# KMO_IO_MV2_2.net
KiCad netlist of a schematic drawn in EAGLE
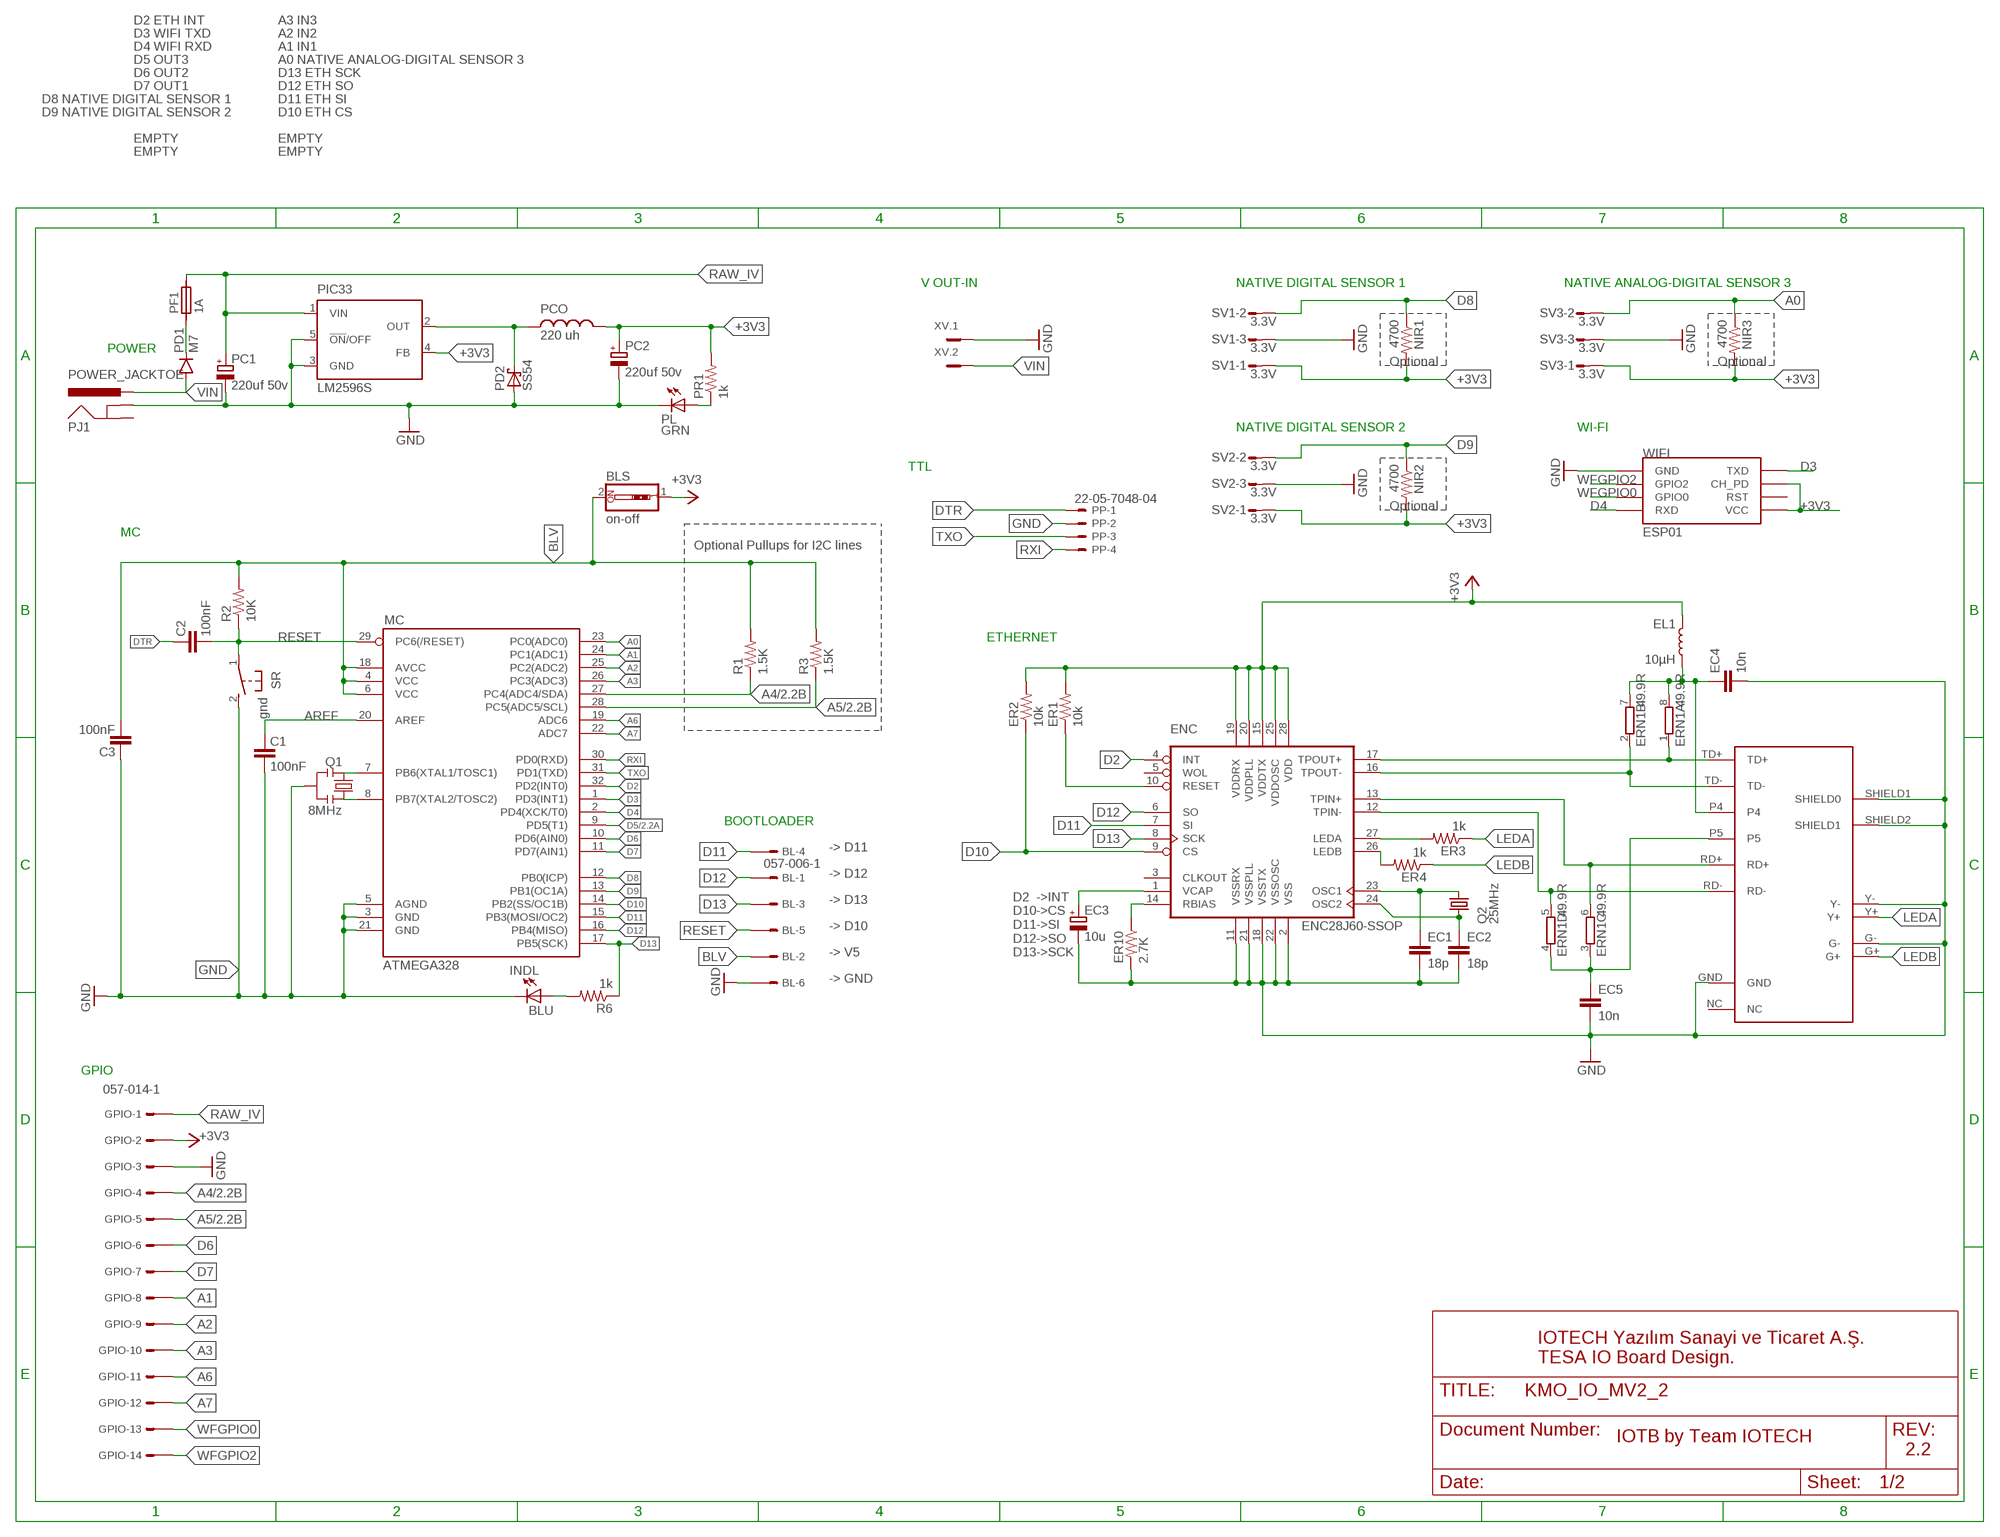
[diagram p0: schematic, sheet 1]
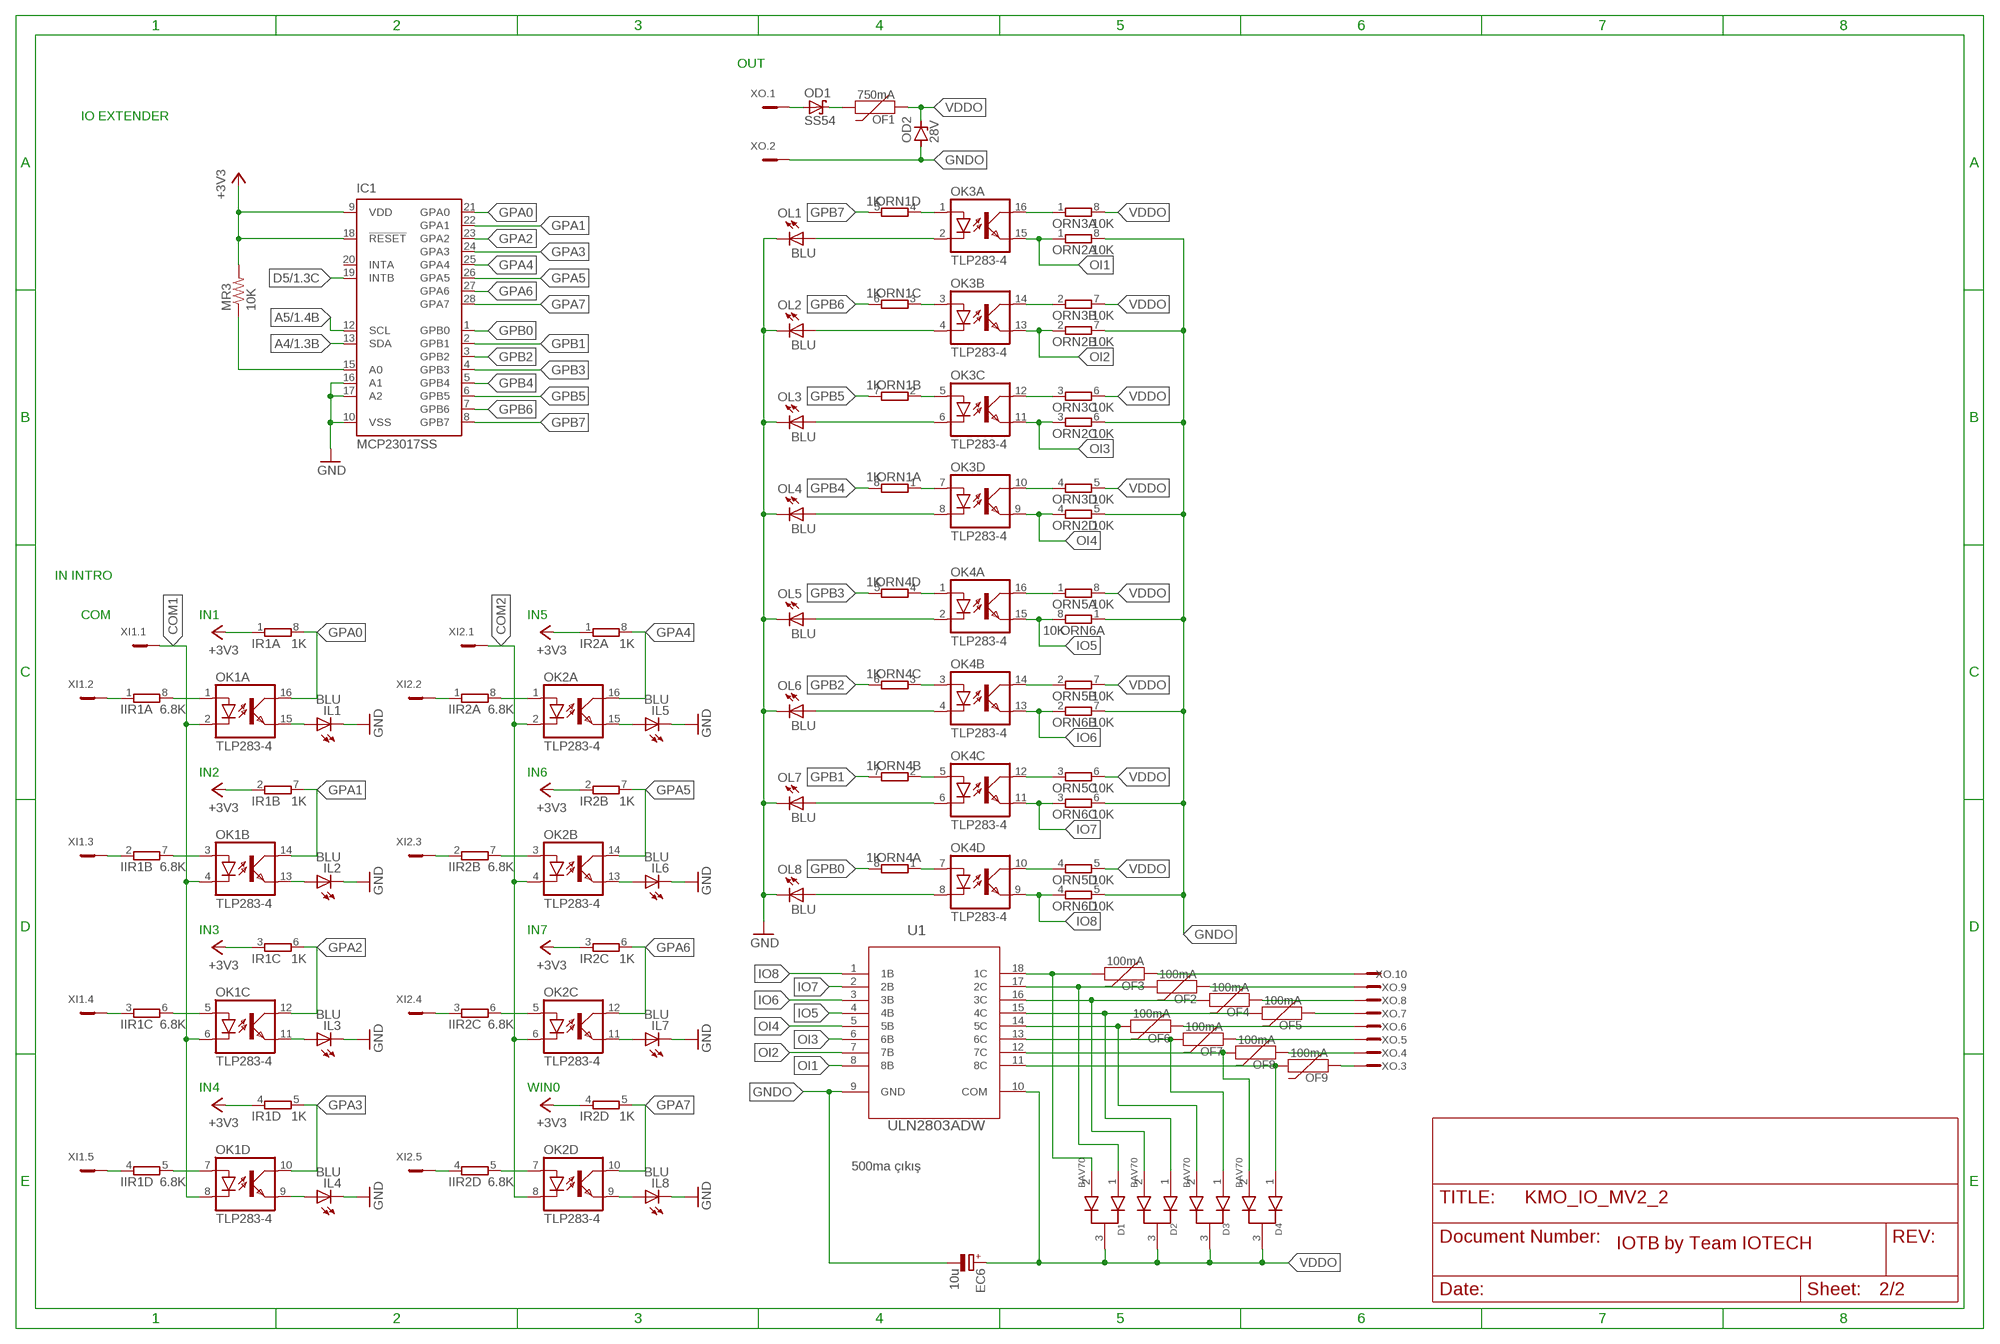
[diagram p1: schematic, sheet 2]

(export (version "E")
  (design (tool "Eeschema 10.0.6"))
  (components
    (comp (ref "BL")
      (value "057-006-1")
      (footprint "eagle-import:057-006-1")
      (libsource (lib "eagle-import") (part "057-006-1"))
    )
    (comp (ref "BLS")
      (value "on-off")
      (footprint "eagle-import:EDG-01")
      (libsource (lib "eagle-import") (part "SW_DIP-1"))
    )
    (comp (ref "C1")
      (value "100nF")
      (footprint "eagle-import:0805")
      (libsource (lib "eagle-import") (part "CAP0805"))
    )
    (comp (ref "C2")
      (value "100nF")
      (footprint "eagle-import:0805")
      (libsource (lib "eagle-import") (part "CAP0805"))
    )
    (comp (ref "C3")
      (value "100nF")
      (footprint "eagle-import:0805")
      (libsource (lib "eagle-import") (part "CAP0805"))
    )
    (comp (ref "EC1")
      (value "18p")
      (footprint "eagle-import:0805")
      (libsource (lib "eagle-import") (part "CAP0805"))
    )
    (comp (ref "EC2")
      (value "18p")
      (footprint "eagle-import:0805")
      (libsource (lib "eagle-import") (part "CAP0805"))
    )
    (comp (ref "EC3")
      (value "10u")
      (footprint "eagle-import:CT3216")
      (libsource (lib "eagle-import") (part "CPOL-EUCT3216"))
    )
    (comp (ref "EC4")
      (value "10n")
      (footprint "eagle-import:0805")
      (libsource (lib "eagle-import") (part "CAP0805"))
    )
    (comp (ref "EC5")
      (value "10n")
      (footprint "eagle-import:0805")
      (libsource (lib "eagle-import") (part "CAP0805"))
    )
    (comp (ref "EL1")
      (value "10µH")
      (footprint "eagle-import:0805")
      (libsource (lib "eagle-import") (part "INDUCTOR-0805-3.3UH"))
    )
    (comp (ref "ENC")
      (value "ENC28J60-SSOP")
      (footprint "eagle-import:SSOP28")
      (libsource (lib "eagle-import") (part "ENC28J60-SSOP"))
    )
    (comp (ref "ER1")
      (value "10k")
      (footprint "eagle-import:0805")
      (libsource (lib "eagle-import") (part "RESISTOR0805-RES"))
    )
    (comp (ref "ER2")
      (value "10k")
      (footprint "eagle-import:0805")
      (libsource (lib "eagle-import") (part "RESISTOR0805-RES"))
    )
    (comp (ref "ER3")
      (value "1k")
      (footprint "eagle-import:0805")
      (libsource (lib "eagle-import") (part "RESISTOR0805-RES"))
    )
    (comp (ref "ER4")
      (value "1k")
      (footprint "eagle-import:0805")
      (libsource (lib "eagle-import") (part "RESISTOR0805-RES"))
    )
    (comp (ref "ER10")
      (value "2.7K")
      (footprint "eagle-import:0805")
      (libsource (lib "eagle-import") (part "RESISTOR0805-RES"))
    )
    (comp (ref "ERN1")
      (value "49.9R")
      (footprint "eagle-import:0603-ARV")
      (libsource (lib "eagle-import") (part "4R-N0603-ARV"))
    )
    (comp (ref "GPIO")
      (value "057-014-1")
      (footprint "eagle-import:057-014-1")
      (libsource (lib "eagle-import") (part "057-014-1"))
    )
    (comp (ref "INDL")
      (value "BLU")
      (footprint "eagle-import:CHIP-LED0805")
      (libsource (lib "eagle-import") (part "LEDCHIP-LED0805"))
    )
    (comp (ref "MC")
      (value "ATMEGA328")
      (footprint "eagle-import:TQFP32-08")
      (libsource (lib "eagle-import") (part "ATMEGA168"))
    )
    (comp (ref "NIR1")
      (value "4700")
      (footprint "eagle-import:0805")
      (libsource (lib "eagle-import") (part "RESISTOR0805-RES"))
    )
    (comp (ref "NIR2")
      (value "4700")
      (footprint "eagle-import:0805")
      (libsource (lib "eagle-import") (part "RESISTOR0805-RES"))
    )
    (comp (ref "NIR3")
      (value "4700")
      (footprint "eagle-import:0805")
      (libsource (lib "eagle-import") (part "RESISTOR0805-RES"))
    )
    (comp (ref "PC1")
      (value "220uf 50v")
      (footprint "eagle-import:140CLH-1010")
      (libsource (lib "eagle-import") (part "CPOL-EU140CLH-1010"))
    )
    (comp (ref "PC2")
      (value "220uf 50v")
      (footprint "eagle-import:140CLH-1010")
      (libsource (lib "eagle-import") (part "CPOL-EU140CLH-1010"))
    )
    (comp (ref "PCO")
      (value "220 uh")
      (footprint "eagle-import:MSS1260")
      (libsource (lib "eagle-import") (part "MSS1260"))
    )
    (comp (ref "PD1")
      (value "M7")
      (footprint "eagle-import:SMA-DIODE")
      (libsource (lib "eagle-import") (part "DIODESMA"))
    )
    (comp (ref "PD2")
      (value "SS54")
      (footprint "eagle-import:SMB")
      (libsource (lib "eagle-import") (part "SCHOTTKY-DIODESMD"))
    )
    (comp (ref "PF1")
      (value "1A")
      (footprint "eagle-import:1820")
      (libsource (lib "eagle-import") (part "SIBA194600"))
    )
    (comp (ref "PIC33")
      (value "LM2596S")
      (footprint "eagle-import:TO263-5")
      (fields (field (name "MF") "NATIONAL SEMICONDUCTOR") (field (name "MPN") "LM2596S-ADJ/NOPB"))
      (libsource (lib "eagle-import") (part "LM2596S"))
    )
    (comp (ref "PJ1")
      (value "POWER_JACKTOE")
      (footprint "eagle-import:POWER_JACK_SMD_OVERPASTE_TOE")
      (libsource (lib "eagle-import") (part "POWER_JACKTOE"))
    )
    (comp (ref "PL")
      (value "GRN")
      (footprint "eagle-import:CHIP-LED0805")
      (libsource (lib "eagle-import") (part "LEDCHIP-LED0805"))
    )
    (comp (ref "PP")
      (value "22-05-7048-04")
      (footprint "eagle-import:7395-04")
      (fields (field (name "MF") "MOLEX"))
      (libsource (lib "eagle-import") (part "22-?-0405-7048"))
    )
    (comp (ref "PR1")
      (value "1k")
      (footprint "eagle-import:0805")
      (libsource (lib "eagle-import") (part "RESISTOR0805-RES"))
    )
    (comp (ref "Q1")
      (value "8MHz")
      (footprint "eagle-import:RESONATOR-SMD-1_1")
      (libsource (lib "eagle-import") (part "RESONATOR1{colon}1"))
    )
    (comp (ref "Q2")
      (value "25MHz")
      (footprint "eagle-import:5.0X3.2_2")
      (libsource (lib "eagle-import") (part "KX-9B"))
    )
    (comp (ref "R1")
      (value "1.5K")
      (footprint "eagle-import:0805")
      (libsource (lib "eagle-import") (part "RESISTOR0805-RES"))
    )
    (comp (ref "R2")
      (value "10K")
      (footprint "eagle-import:0805")
      (libsource (lib "eagle-import") (part "RESISTOR0805-RES"))
    )
    (comp (ref "R3")
      (value "1.5K")
      (footprint "eagle-import:0805")
      (libsource (lib "eagle-import") (part "RESISTOR0805-RES"))
    )
    (comp (ref "R6")
      (value "1k")
      (footprint "eagle-import:0805")
      (libsource (lib "eagle-import") (part "RESISTOR0805-RES"))
    )
    (comp (ref "SR")
      (value "gnd")
      (footprint "eagle-import:B3F-31XX")
      (fields (field (name "MPN") "B3F-3100"))
      (libsource (lib "eagle-import") (part "31-XX"))
    )
    (comp (ref "SV1")
      (value "3.3V")
      (footprint "eagle-import:S03P")
      (libsource (lib "eagle-import") (part "S03P"))
    )
    (comp (ref "SV2")
      (value "3.3V")
      (footprint "eagle-import:S03P")
      (libsource (lib "eagle-import") (part "S03P"))
    )
    (comp (ref "SV3")
      (value "3.3V")
      (footprint "eagle-import:S03P")
      (libsource (lib "eagle-import") (part "S03P"))
    )
    (comp (ref "U$2")
      (value "HR911105A")
      (footprint "eagle-import:RJ45")
      (libsource (lib "eagle-import") (part "HR911105A"))
    )
    (comp (ref "WIFI")
      (value "ESP01")
      (footprint "eagle-import:ESP01")
      (libsource (lib "eagle-import") (part "ESP01"))
    )
    (comp (ref "XV")
      (value "MC2")
      (footprint "eagle-import:MC2")
      (libsource (lib "eagle-import") (part "MC2"))
    )
    (comp (ref "D1")
      (value "BAV70")
      (footprint "eagle-import:SOT-23-3")
      (fields (field (name "MF") "Multicomp") (field (name "MP") "BAV70+"))
      (libsource (lib "eagle-import") (part "BAV70"))
    )
    (comp (ref "D2")
      (value "BAV70")
      (footprint "eagle-import:SOT-23-3")
      (fields (field (name "MF") "Multicomp") (field (name "MP") "BAV70+"))
      (libsource (lib "eagle-import") (part "BAV70"))
    )
    (comp (ref "D3")
      (value "BAV70")
      (footprint "eagle-import:SOT-23-3")
      (fields (field (name "MF") "Multicomp") (field (name "MP") "BAV70+"))
      (libsource (lib "eagle-import") (part "BAV70"))
    )
    (comp (ref "D4")
      (value "BAV70")
      (footprint "eagle-import:SOT-23-3")
      (fields (field (name "MF") "Multicomp") (field (name "MP") "BAV70+"))
      (libsource (lib "eagle-import") (part "BAV70"))
    )
    (comp (ref "EC6")
      (value "10u")
      (footprint "eagle-import:CT3216")
      (libsource (lib "eagle-import") (part "CPOL-EUCT3216"))
    )
    (comp (ref "IC1")
      (value "MCP23017SS")
      (footprint "eagle-import:SSOP28")
      (fields (field (name "MF") "MICROCHIP") (field (name "MPN") "MCP23017-E/SS"))
      (libsource (lib "eagle-import") (part "MCP23017SS"))
    )
    (comp (ref "IIR1")
      (value "6.8K")
      (footprint "eagle-import:0603-ARV")
      (libsource (lib "eagle-import") (part "4R-N0603-ARV"))
    )
    (comp (ref "IIR2")
      (value "6.8K")
      (footprint "eagle-import:0603-ARV")
      (libsource (lib "eagle-import") (part "4R-N0603-ARV"))
    )
    (comp (ref "IL1")
      (value "BLU")
      (footprint "eagle-import:CHIP-LED0805")
      (libsource (lib "eagle-import") (part "LEDCHIP-LED0805"))
    )
    (comp (ref "IL2")
      (value "BLU")
      (footprint "eagle-import:CHIP-LED0805")
      (libsource (lib "eagle-import") (part "LEDCHIP-LED0805"))
    )
    (comp (ref "IL3")
      (value "BLU")
      (footprint "eagle-import:CHIP-LED0805")
      (libsource (lib "eagle-import") (part "LEDCHIP-LED0805"))
    )
    (comp (ref "IL4")
      (value "BLU")
      (footprint "eagle-import:CHIP-LED0805")
      (libsource (lib "eagle-import") (part "LEDCHIP-LED0805"))
    )
    (comp (ref "IL5")
      (value "BLU")
      (footprint "eagle-import:CHIP-LED0805")
      (libsource (lib "eagle-import") (part "LEDCHIP-LED0805"))
    )
    (comp (ref "IL6")
      (value "BLU")
      (footprint "eagle-import:CHIP-LED0805")
      (libsource (lib "eagle-import") (part "LEDCHIP-LED0805"))
    )
    (comp (ref "IL7")
      (value "BLU")
      (footprint "eagle-import:CHIP-LED0805")
      (libsource (lib "eagle-import") (part "LEDCHIP-LED0805"))
    )
    (comp (ref "IL8")
      (value "BLU")
      (footprint "eagle-import:CHIP-LED0805")
      (libsource (lib "eagle-import") (part "LEDCHIP-LED0805"))
    )
    (comp (ref "IR1")
      (value "1K")
      (footprint "eagle-import:0603-ARV")
      (libsource (lib "eagle-import") (part "4R-N0603-ARV"))
    )
    (comp (ref "IR2")
      (value "1K")
      (footprint "eagle-import:0603-ARV")
      (libsource (lib "eagle-import") (part "4R-N0603-ARV"))
    )
    (comp (ref "MR3")
      (value "10K")
      (footprint "eagle-import:0805")
      (libsource (lib "eagle-import") (part "RESISTOR0805-RES"))
    )
    (comp (ref "OD1")
      (value "SS54")
      (footprint "eagle-import:SMB")
      (libsource (lib "eagle-import") (part "SCHOTTKY-DIODESMD"))
    )
    (comp (ref "OD2")
      (value "28V")
      (footprint "eagle-import:SMB")
      (libsource (lib "eagle-import") (part "ZENER-DIODESMB"))
    )
    (comp (ref "OF1")
      (value "750mA")
      (footprint "eagle-import:1206")
      (libsource (lib "eagle-import") (part "PPTC_0.75A"))
    )
    (comp (ref "OF2")
      (value "100mA")
      (footprint "eagle-import:1206")
      (libsource (lib "eagle-import") (part "PPTC_0.75A"))
    )
    (comp (ref "OF3")
      (value "100mA")
      (footprint "eagle-import:1206")
      (libsource (lib "eagle-import") (part "PPTC_0.75A"))
    )
    (comp (ref "OF4")
      (value "100mA")
      (footprint "eagle-import:1206")
      (libsource (lib "eagle-import") (part "PPTC_0.75A"))
    )
    (comp (ref "OF5")
      (value "100mA")
      (footprint "eagle-import:1206")
      (libsource (lib "eagle-import") (part "PPTC_0.75A"))
    )
    (comp (ref "OF6")
      (value "100mA")
      (footprint "eagle-import:1206")
      (libsource (lib "eagle-import") (part "PPTC_0.75A"))
    )
    (comp (ref "OF7")
      (value "100mA")
      (footprint "eagle-import:1206")
      (libsource (lib "eagle-import") (part "PPTC_0.75A"))
    )
    (comp (ref "OF8")
      (value "100mA")
      (footprint "eagle-import:1206")
      (libsource (lib "eagle-import") (part "PPTC_0.75A"))
    )
    (comp (ref "OF9")
      (value "100mA")
      (footprint "eagle-import:1206")
      (libsource (lib "eagle-import") (part "PPTC_0.75A"))
    )
    (comp (ref "OK1")
      (value "TLP283-4")
      (footprint "eagle-import:MINI-FLAT-16")
      (fields (field (name "SPICEPREFIX") "O"))
      (libsource (lib "eagle-import") (part "TLP283-4"))
    )
    (comp (ref "OK2")
      (value "TLP283-4")
      (footprint "eagle-import:MINI-FLAT-16")
      (fields (field (name "SPICEPREFIX") "O"))
      (libsource (lib "eagle-import") (part "TLP283-4"))
    )
    (comp (ref "OK3")
      (value "TLP283-4")
      (footprint "eagle-import:MINI-FLAT-16")
      (libsource (lib "eagle-import") (part "TLP283-4"))
    )
    (comp (ref "OK4")
      (value "TLP283-4")
      (footprint "eagle-import:MINI-FLAT-16")
      (libsource (lib "eagle-import") (part "TLP283-4"))
    )
    (comp (ref "OL1")
      (value "BLU")
      (footprint "eagle-import:CHIP-LED0805")
      (libsource (lib "eagle-import") (part "LEDCHIP-LED0805"))
    )
    (comp (ref "OL2")
      (value "BLU")
      (footprint "eagle-import:CHIP-LED0805")
      (libsource (lib "eagle-import") (part "LEDCHIP-LED0805"))
    )
    (comp (ref "OL3")
      (value "BLU")
      (footprint "eagle-import:CHIP-LED0805")
      (libsource (lib "eagle-import") (part "LEDCHIP-LED0805"))
    )
    (comp (ref "OL4")
      (value "BLU")
      (footprint "eagle-import:CHIP-LED0805")
      (libsource (lib "eagle-import") (part "LEDCHIP-LED0805"))
    )
    (comp (ref "OL5")
      (value "BLU")
      (footprint "eagle-import:CHIP-LED0805")
      (libsource (lib "eagle-import") (part "LEDCHIP-LED0805"))
    )
    (comp (ref "OL6")
      (value "BLU")
      (footprint "eagle-import:CHIP-LED0805")
      (libsource (lib "eagle-import") (part "LEDCHIP-LED0805"))
    )
    (comp (ref "OL7")
      (value "BLU")
      (footprint "eagle-import:CHIP-LED0805")
      (libsource (lib "eagle-import") (part "LEDCHIP-LED0805"))
    )
    (comp (ref "OL8")
      (value "BLU")
      (footprint "eagle-import:CHIP-LED0805")
      (libsource (lib "eagle-import") (part "LEDCHIP-LED0805"))
    )
    (comp (ref "ORN1")
      (value "1K")
      (footprint "eagle-import:0603-ARV")
      (libsource (lib "eagle-import") (part "4R-N0603-ARV"))
    )
    (comp (ref "ORN2")
      (value "10K")
      (footprint "eagle-import:0603-ARV")
      (libsource (lib "eagle-import") (part "4R-N0603-ARV"))
    )
    (comp (ref "ORN3")
      (value "10K")
      (footprint "eagle-import:0603-ARV")
      (libsource (lib "eagle-import") (part "4R-N0603-ARV"))
    )
    (comp (ref "ORN4")
      (value "1K")
      (footprint "eagle-import:0603-ARV")
      (libsource (lib "eagle-import") (part "4R-N0603-ARV"))
    )
    (comp (ref "ORN5")
      (value "10K")
      (footprint "eagle-import:0603-ARV")
      (libsource (lib "eagle-import") (part "4R-N0603-ARV"))
    )
    (comp (ref "ORN6")
      (value "10K")
      (footprint "eagle-import:0603-ARV")
      (libsource (lib "eagle-import") (part "4R-N0603-ARV"))
    )
    (comp (ref "U1")
      (value "ULN2803ADW")
      (footprint "eagle-import:SOIC127P1030X265-18N")
      (libsource (lib "eagle-import") (part "ULN2803ADW"))
    )
    (comp (ref "XI1")
      (value "MC5")
      (footprint "eagle-import:MC5")
      (libsource (lib "eagle-import") (part "MC5"))
    )
    (comp (ref "XI2")
      (value "MC5")
      (footprint "eagle-import:MC5")
      (libsource (lib "eagle-import") (part "MC5"))
    )
    (comp (ref "XO")
      (value "MC10")
      (footprint "eagle-import:MC10")
      (libsource (lib "eagle-import") (part "MC10"))
    )
  )
  (nets
    (net (code "1") (name "+3V3") (class "Default")
      (node (ref "BLS") (pin "1") (pinfunction "1_1") (pintype "passive"))
      (node (ref "EL1") (pin "1") (pinfunction "1_1") (pintype "passive"))
      (node (ref "ENC") (pin "15") (pinfunction "VDDTX_15") (pintype "power_in"))
      (node (ref "ENC") (pin "19") (pinfunction "VDDRX_19") (pintype "power_in"))
      (node (ref "ENC") (pin "20") (pinfunction "VDDPLL_20") (pintype "power_in"))
      (node (ref "ENC") (pin "25") (pinfunction "VDDOSC_25") (pintype "power_in"))
      (node (ref "ENC") (pin "28") (pinfunction "VDD_28") (pintype "power_in"))
      (node (ref "ER1") (pin "2") (pinfunction "2_2") (pintype "passive"))
      (node (ref "ER2") (pin "2") (pinfunction "2_2") (pintype "passive"))
      (node (ref "GPIO") (pin "2") (pinfunction "S_2") (pintype "passive"))
      (node (ref "IC1") (pin "18") (pinfunction "~{RESET}_18") (pintype "input"))
      (node (ref "IC1") (pin "9") (pinfunction "VDD_9") (pintype "power_in"))
      (node (ref "IR1") (pin "1") (pinfunction "1_1") (pintype "passive"))
      (node (ref "IR1") (pin "2") (pinfunction "1_2") (pintype "passive"))
      (node (ref "IR1") (pin "3") (pinfunction "1_3") (pintype "passive"))
      (node (ref "IR1") (pin "4") (pinfunction "1_4") (pintype "passive"))
      (node (ref "IR2") (pin "1") (pinfunction "1_1") (pintype "passive"))
      (node (ref "IR2") (pin "2") (pinfunction "1_2") (pintype "passive"))
      (node (ref "IR2") (pin "3") (pinfunction "1_3") (pintype "passive"))
      (node (ref "IR2") (pin "4") (pinfunction "1_4") (pintype "passive"))
      (node (ref "MR3") (pin "2") (pinfunction "2_2") (pintype "passive"))
      (node (ref "NIR1") (pin "2") (pinfunction "2_2") (pintype "passive"))
      (node (ref "NIR2") (pin "2") (pinfunction "2_2") (pintype "passive"))
      (node (ref "NIR3") (pin "2") (pinfunction "2_2") (pintype "passive"))
      (node (ref "PC2") (pin "+") (pinfunction "+_+") (pintype "passive"))
      (node (ref "PCO") (pin "P$1") (pinfunction "P$1_P$1") (pintype "passive"))
      (node (ref "PIC33") (pin "4") (pinfunction "FB_4") (pintype "input"))
      (node (ref "PR1") (pin "2") (pinfunction "2_2") (pintype "passive"))
      (node (ref "SV1") (pin "1") (pinfunction "S_1") (pintype "passive"))
      (node (ref "SV2") (pin "1") (pinfunction "S_1") (pintype "passive"))
      (node (ref "SV3") (pin "1") (pinfunction "S_1") (pintype "passive"))
      (node (ref "WIFI") (pin "CH_PD") (pinfunction "CH_PD_CH_PD") (pintype "bidirectional"))
      (node (ref "WIFI") (pin "VCC") (pinfunction "VCC_VCC") (pintype "bidirectional"))
    )
    (net (code "2") (name "A0") (class "Default")
      (node (ref "MC") (pin "23") (pinfunction "PC0(ADC0)_23") (pintype "bidirectional"))
      (node (ref "NIR3") (pin "1") (pinfunction "1_1") (pintype "passive"))
      (node (ref "SV3") (pin "2") (pinfunction "S_2") (pintype "passive"))
    )
    (net (code "3") (name "A1") (class "Default")
      (node (ref "GPIO") (pin "8") (pinfunction "S_8") (pintype "passive"))
      (node (ref "MC") (pin "24") (pinfunction "PC1(ADC1)_24") (pintype "bidirectional"))
    )
    (net (code "4") (name "A2") (class "Default")
      (node (ref "GPIO") (pin "9") (pinfunction "S_9") (pintype "passive"))
      (node (ref "MC") (pin "25") (pinfunction "PC2(ADC2)_25") (pintype "bidirectional"))
    )
    (net (code "5") (name "A3") (class "Default")
      (node (ref "GPIO") (pin "10") (pinfunction "S_10") (pintype "passive"))
      (node (ref "MC") (pin "26") (pinfunction "PC3(ADC3)_26") (pintype "bidirectional"))
    )
    (net (code "6") (name "A4") (class "Default")
      (node (ref "GPIO") (pin "4") (pinfunction "S_4") (pintype "passive"))
      (node (ref "IC1") (pin "13") (pinfunction "SDA_13") (pintype "bidirectional"))
      (node (ref "MC") (pin "27") (pinfunction "PC4(ADC4/SDA)_27") (pintype "bidirectional"))
      (node (ref "R1") (pin "1") (pinfunction "1_1") (pintype "passive"))
    )
    (net (code "7") (name "A5") (class "Default")
      (node (ref "GPIO") (pin "5") (pinfunction "S_5") (pintype "passive"))
      (node (ref "IC1") (pin "12") (pinfunction "SCL_12") (pintype "input"))
      (node (ref "MC") (pin "28") (pinfunction "PC5(ADC5/SCL)_28") (pintype "bidirectional"))
      (node (ref "R3") (pin "1") (pinfunction "1_1") (pintype "passive"))
    )
    (net (code "8") (name "A6") (class "Default")
      (node (ref "GPIO") (pin "11") (pinfunction "S_11") (pintype "passive"))
      (node (ref "MC") (pin "19") (pinfunction "ADC6_19") (pintype "bidirectional"))
    )
    (net (code "9") (name "A7") (class "Default")
      (node (ref "GPIO") (pin "12") (pinfunction "S_12") (pintype "passive"))
      (node (ref "MC") (pin "22") (pinfunction "ADC7_22") (pintype "bidirectional"))
    )
    (net (code "10") (name "AREF") (class "Default")
      (node (ref "C1") (pin "2") (pinfunction "2_2") (pintype "passive"))
      (node (ref "MC") (pin "20") (pinfunction "AREF_20") (pintype "bidirectional"))
    )
    (net (code "11") (name "BLV") (class "Default")
      (node (ref "BL") (pin "2") (pinfunction "S_2") (pintype "passive"))
      (node (ref "BLS") (pin "2") (pinfunction "2_2") (pintype "passive"))
      (node (ref "C3") (pin "1") (pinfunction "1_1") (pintype "passive"))
      (node (ref "MC") (pin "18") (pinfunction "AVCC_18") (pintype "bidirectional"))
      (node (ref "MC") (pin "4") (pinfunction "VCC_4") (pintype "bidirectional"))
      (node (ref "MC") (pin "6") (pinfunction "VCC_6") (pintype "bidirectional"))
      (node (ref "R1") (pin "2") (pinfunction "2_2") (pintype "passive"))
      (node (ref "R2") (pin "2") (pinfunction "2_2") (pintype "passive"))
      (node (ref "R3") (pin "2") (pinfunction "2_2") (pintype "passive"))
    )
    (net (code "12") (name "COM1") (class "Default")
      (node (ref "OK1") (pin "2") (pinfunction "C_2") (pintype "passive"))
      (node (ref "OK1") (pin "4") (pinfunction "C_4") (pintype "passive"))
      (node (ref "OK1") (pin "6") (pinfunction "C_6") (pintype "passive"))
      (node (ref "OK1") (pin "8") (pinfunction "C_8") (pintype "passive"))
      (node (ref "XI1") (pin "1") (pinfunction "SK_1") (pintype "passive"))
    )
    (net (code "13") (name "COM2") (class "Default")
      (node (ref "OK2") (pin "2") (pinfunction "C_2") (pintype "passive"))
      (node (ref "OK2") (pin "4") (pinfunction "C_4") (pintype "passive"))
      (node (ref "OK2") (pin "6") (pinfunction "C_6") (pintype "passive"))
      (node (ref "OK2") (pin "8") (pinfunction "C_8") (pintype "passive"))
      (node (ref "XI2") (pin "1") (pinfunction "SK_1") (pintype "passive"))
    )
    (net (code "14") (name "D2") (class "Default")
      (node (ref "ENC") (pin "4") (pinfunction "INT_4") (pintype "output"))
      (node (ref "MC") (pin "32") (pinfunction "PD2(INT0)_32") (pintype "bidirectional"))
    )
    (net (code "15") (name "D3") (class "Default")
      (node (ref "MC") (pin "1") (pinfunction "PD3(INT1)_1") (pintype "bidirectional"))
      (node (ref "WIFI") (pin "TX") (pinfunction "TXD_TX") (pintype "bidirectional"))
    )
    (net (code "16") (name "D4") (class "Default")
      (node (ref "MC") (pin "2") (pinfunction "PD4(XCK/T0)_2") (pintype "bidirectional"))
      (node (ref "WIFI") (pin "RX") (pinfunction "RXD_RX") (pintype "bidirectional"))
    )
    (net (code "17") (name "D5") (class "Default")
      (node (ref "IC1") (pin "19") (pinfunction "INTB_19") (pintype "output"))
      (node (ref "MC") (pin "9") (pinfunction "PD5(T1)_9") (pintype "bidirectional"))
    )
    (net (code "18") (name "D6") (class "Default")
      (node (ref "GPIO") (pin "6") (pinfunction "S_6") (pintype "passive"))
      (node (ref "MC") (pin "10") (pinfunction "PD6(AIN0)_10") (pintype "bidirectional"))
    )
    (net (code "19") (name "D7") (class "Default")
      (node (ref "GPIO") (pin "7") (pinfunction "S_7") (pintype "passive"))
      (node (ref "MC") (pin "11") (pinfunction "PD7(AIN1)_11") (pintype "bidirectional"))
    )
    (net (code "20") (name "D8") (class "Default")
      (node (ref "MC") (pin "12") (pinfunction "PB0(ICP)_12") (pintype "bidirectional"))
      (node (ref "NIR1") (pin "1") (pinfunction "1_1") (pintype "passive"))
      (node (ref "SV1") (pin "2") (pinfunction "S_2") (pintype "passive"))
    )
    (net (code "21") (name "D9") (class "Default")
      (node (ref "MC") (pin "13") (pinfunction "PB1(OC1A)_13") (pintype "bidirectional"))
      (node (ref "NIR2") (pin "1") (pinfunction "1_1") (pintype "passive"))
      (node (ref "SV2") (pin "2") (pinfunction "S_2") (pintype "passive"))
    )
    (net (code "22") (name "D10") (class "Default")
      (node (ref "ENC") (pin "9") (pinfunction "CS_9") (pintype "input"))
      (node (ref "ER2") (pin "1") (pinfunction "1_1") (pintype "passive"))
      (node (ref "MC") (pin "14") (pinfunction "PB2(SS/OC1B)_14") (pintype "bidirectional"))
    )
    (net (code "23") (name "D11") (class "Default")
      (node (ref "BL") (pin "4") (pinfunction "S_4") (pintype "passive"))
      (node (ref "ENC") (pin "7") (pinfunction "SI_7") (pintype "input"))
      (node (ref "MC") (pin "15") (pinfunction "PB3(MOSI/OC2)_15") (pintype "bidirectional"))
    )
    (net (code "24") (name "D12") (class "Default")
      (node (ref "BL") (pin "1") (pinfunction "S_1") (pintype "passive"))
      (node (ref "ENC") (pin "6") (pinfunction "SO_6") (pintype "output"))
      (node (ref "MC") (pin "16") (pinfunction "PB4(MISO)_16") (pintype "bidirectional"))
    )
    (net (code "25") (name "D13") (class "Default")
      (node (ref "BL") (pin "3") (pinfunction "S_3") (pintype "passive"))
      (node (ref "ENC") (pin "8") (pinfunction "SCK_8") (pintype "input"))
      (node (ref "MC") (pin "17") (pinfunction "PB5(SCK)_17") (pintype "bidirectional"))
      (node (ref "R6") (pin "1") (pinfunction "1_1") (pintype "passive"))
    )
    (net (code "26") (name "DTR") (class "Default")
      (node (ref "C2") (pin "2") (pinfunction "2_2") (pintype "passive"))
      (node (ref "PP") (pin "1") (pinfunction "S_1") (pintype "passive"))
    )
    (net (code "27") (name "GND") (class "Default")
      (node (ref "BL") (pin "6") (pinfunction "S_6") (pintype "passive"))
      (node (ref "C1") (pin "1") (pinfunction "1_1") (pintype "passive"))
      (node (ref "C3") (pin "2") (pinfunction "2_2") (pintype "passive"))
      (node (ref "EC1") (pin "2") (pinfunction "2_2") (pintype "passive"))
      (node (ref "EC2") (pin "2") (pinfunction "2_2") (pintype "passive"))
      (node (ref "EC3") (pin "-") (pinfunction "-_-") (pintype "passive"))
      (node (ref "EC4") (pin "2") (pinfunction "2_2") (pintype "passive"))
      (node (ref "EC5") (pin "2") (pinfunction "2_2") (pintype "passive"))
      (node (ref "ENC") (pin "11") (pinfunction "VSSRX_11") (pintype "power_in"))
      (node (ref "ENC") (pin "18") (pinfunction "VSSTX_18") (pintype "power_in"))
      (node (ref "ENC") (pin "2") (pinfunction "VSS_2") (pintype "power_in"))
      (node (ref "ENC") (pin "21") (pinfunction "VSSPLL_21") (pintype "power_in"))
      (node (ref "ENC") (pin "22") (pinfunction "VSSOSC_22") (pintype "power_in"))
      (node (ref "ER10") (pin "2") (pinfunction "2_2") (pintype "passive"))
      (node (ref "GPIO") (pin "3") (pinfunction "S_3") (pintype "passive"))
      (node (ref "IC1") (pin "10") (pinfunction "VSS_10") (pintype "power_in"))
      (node (ref "IC1") (pin "16") (pinfunction "A1_16") (pintype "input"))
      (node (ref "IC1") (pin "17") (pinfunction "A2_17") (pintype "input"))
      (node (ref "IL1") (pin "C") (pinfunction "C_C") (pintype "passive"))
      (node (ref "IL2") (pin "C") (pinfunction "C_C") (pintype "passive"))
      (node (ref "IL3") (pin "C") (pinfunction "C_C") (pintype "passive"))
      (node (ref "IL4") (pin "C") (pinfunction "C_C") (pintype "passive"))
      (node (ref "IL5") (pin "C") (pinfunction "C_C") (pintype "passive"))
      (node (ref "IL6") (pin "C") (pinfunction "C_C") (pintype "passive"))
      (node (ref "IL7") (pin "C") (pinfunction "C_C") (pintype "passive"))
      (node (ref "IL8") (pin "C") (pinfunction "C_C") (pintype "passive"))
      (node (ref "INDL") (pin "C") (pinfunction "C_C") (pintype "passive"))
      (node (ref "MC") (pin "21") (pinfunction "GND_21") (pintype "bidirectional"))
      (node (ref "MC") (pin "3") (pinfunction "GND_3") (pintype "bidirectional"))
      (node (ref "MC") (pin "5") (pinfunction "AGND_5") (pintype "bidirectional"))
      (node (ref "OL1") (pin "C") (pinfunction "C_C") (pintype "passive"))
      (node (ref "OL2") (pin "C") (pinfunction "C_C") (pintype "passive"))
      (node (ref "OL3") (pin "C") (pinfunction "C_C") (pintype "passive"))
      (node (ref "OL4") (pin "C") (pinfunction "C_C") (pintype "passive"))
      (node (ref "OL5") (pin "C") (pinfunction "C_C") (pintype "passive"))
      (node (ref "OL6") (pin "C") (pinfunction "C_C") (pintype "passive"))
      (node (ref "OL7") (pin "C") (pinfunction "C_C") (pintype "passive"))
      (node (ref "OL8") (pin "C") (pinfunction "C_C") (pintype "passive"))
      (node (ref "PC1") (pin "-") (pinfunction "-_-") (pintype "passive"))
      (node (ref "PC2") (pin "-") (pinfunction "-_-") (pintype "passive"))
      (node (ref "PD2") (pin "A") (pinfunction "A_A") (pintype "passive"))
      (node (ref "PIC33") (pin "3") (pinfunction "GND_3") (pintype "power_in"))
      (node (ref "PIC33") (pin "5") (pinfunction "~{ON}/OFF_5") (pintype "input"))
      (node (ref "PJ1") (pin "GND") (pinfunction "GNDBREAK_GND") (pintype "bidirectional"))
      (node (ref "PL") (pin "C") (pinfunction "C_C") (pintype "passive"))
      (node (ref "PP") (pin "2") (pinfunction "S_2") (pintype "passive"))
      (node (ref "Q1") (pin "2") (pinfunction "2_2") (pintype "passive"))
      (node (ref "SR") (pin "2") (pinfunction "S_2") (pintype "passive"))
      (node (ref "SV1") (pin "3") (pinfunction "S_3") (pintype "passive"))
      (node (ref "SV2") (pin "3") (pinfunction "S_3") (pintype "passive"))
      (node (ref "SV3") (pin "3") (pinfunction "S_3") (pintype "passive"))
      (node (ref "U$2") (pin "G-") (pinfunction "G-_G-") (pintype "bidirectional"))
      (node (ref "U$2") (pin "GND") (pinfunction "GND_GND") (pintype "bidirectional"))
      (node (ref "U$2") (pin "SHIELD1") (pinfunction "SHIELD0_SHIELD1") (pintype "bidirectional"))
      (node (ref "U$2") (pin "SHIELD2") (pinfunction "SHIELD1_SHIELD2") (pintype "bidirectional"))
      (node (ref "U$2") (pin "Y-") (pinfunction "Y-_Y-") (pintype "bidirectional"))
      (node (ref "WIFI") (pin "GND") (pinfunction "GND_GND") (pintype "bidirectional"))
      (node (ref "XV") (pin "1") (pinfunction "SK_1") (pintype "passive"))
    )
    (net (code "28") (name "GNDO") (class "Default")
      (node (ref "EC6") (pin "-") (pinfunction "-_-") (pintype "passive"))
      (node (ref "OD2") (pin "A") (pinfunction "A_A") (pintype "passive"))
      (node (ref "ORN2") (pin "5") (pinfunction "2_5") (pintype "passive"))
      (node (ref "ORN2") (pin "6") (pinfunction "2_6") (pintype "passive"))
      (node (ref "ORN2") (pin "7") (pinfunction "2_7") (pintype "passive"))
      (node (ref "ORN2") (pin "8") (pinfunction "2_8") (pintype "passive"))
      (node (ref "ORN6") (pin "1") (pinfunction "1_1") (pintype "passive"))
      (node (ref "ORN6") (pin "5") (pinfunction "2_5") (pintype "passive"))
      (node (ref "ORN6") (pin "6") (pinfunction "2_6") (pintype "passive"))
      (node (ref "ORN6") (pin "7") (pinfunction "2_7") (pintype "passive"))
      (node (ref "U1") (pin "9") (pinfunction "GND_9") (pintype "passive"))
      (node (ref "XO") (pin "2") (pinfunction "SK_2") (pintype "passive"))
    )
    (net (code "29") (name "GPA0") (class "Default")
      (node (ref "IC1") (pin "21") (pinfunction "GPA0_21") (pintype "bidirectional"))
      (node (ref "IR1") (pin "8") (pinfunction "2_8") (pintype "passive"))
      (node (ref "OK1") (pin "16") (pinfunction "COL_16") (pintype "passive"))
    )
    (net (code "30") (name "GPA1") (class "Default")
      (node (ref "IC1") (pin "22") (pinfunction "GPA1_22") (pintype "bidirectional"))
      (node (ref "IR1") (pin "7") (pinfunction "2_7") (pintype "passive"))
      (node (ref "OK1") (pin "14") (pinfunction "COL_14") (pintype "passive"))
    )
    (net (code "31") (name "GPA2") (class "Default")
      (node (ref "IC1") (pin "23") (pinfunction "GPA2_23") (pintype "bidirectional"))
      (node (ref "IR1") (pin "6") (pinfunction "2_6") (pintype "passive"))
      (node (ref "OK1") (pin "12") (pinfunction "COL_12") (pintype "passive"))
    )
    (net (code "32") (name "GPA3") (class "Default")
      (node (ref "IC1") (pin "24") (pinfunction "GPA3_24") (pintype "bidirectional"))
      (node (ref "IR1") (pin "5") (pinfunction "2_5") (pintype "passive"))
      (node (ref "OK1") (pin "10") (pinfunction "COL_10") (pintype "passive"))
    )
    (net (code "33") (name "GPA4") (class "Default")
      (node (ref "IC1") (pin "25") (pinfunction "GPA4_25") (pintype "bidirectional"))
      (node (ref "IR2") (pin "8") (pinfunction "2_8") (pintype "passive"))
      (node (ref "OK2") (pin "16") (pinfunction "COL_16") (pintype "passive"))
    )
    (net (code "34") (name "GPA5") (class "Default")
      (node (ref "IC1") (pin "26") (pinfunction "GPA5_26") (pintype "bidirectional"))
      (node (ref "IR2") (pin "7") (pinfunction "2_7") (pintype "passive"))
      (node (ref "OK2") (pin "14") (pinfunction "COL_14") (pintype "passive"))
    )
    (net (code "35") (name "GPA6") (class "Default")
      (node (ref "IC1") (pin "27") (pinfunction "GPA6_27") (pintype "bidirectional"))
      (node (ref "IR2") (pin "6") (pinfunction "2_6") (pintype "passive"))
      (node (ref "OK2") (pin "12") (pinfunction "COL_12") (pintype "passive"))
    )
    (net (code "36") (name "GPA7") (class "Default")
      (node (ref "IC1") (pin "28") (pinfunction "GPA7_28") (pintype "bidirectional"))
      (node (ref "IR2") (pin "5") (pinfunction "2_5") (pintype "passive"))
      (node (ref "OK2") (pin "10") (pinfunction "COL_10") (pintype "passive"))
    )
    (net (code "37") (name "GPB0") (class "Default")
      (node (ref "IC1") (pin "1") (pinfunction "GPB0_1") (pintype "bidirectional"))
      (node (ref "ORN4") (pin "8") (pinfunction "2_8") (pintype "passive"))
    )
    (net (code "38") (name "GPB1") (class "Default")
      (node (ref "IC1") (pin "2") (pinfunction "GPB1_2") (pintype "bidirectional"))
      (node (ref "ORN4") (pin "7") (pinfunction "2_7") (pintype "passive"))
    )
    (net (code "39") (name "GPB2") (class "Default")
      (node (ref "IC1") (pin "3") (pinfunction "GPB2_3") (pintype "bidirectional"))
      (node (ref "ORN4") (pin "6") (pinfunction "2_6") (pintype "passive"))
    )
    (net (code "40") (name "GPB3") (class "Default")
      (node (ref "IC1") (pin "4") (pinfunction "GPB3_4") (pintype "bidirectional"))
      (node (ref "ORN4") (pin "5") (pinfunction "2_5") (pintype "passive"))
    )
    (net (code "41") (name "GPB4") (class "Default")
      (node (ref "IC1") (pin "5") (pinfunction "GPB4_5") (pintype "bidirectional"))
      (node (ref "ORN1") (pin "8") (pinfunction "2_8") (pintype "passive"))
    )
    (net (code "42") (name "GPB5") (class "Default")
      (node (ref "IC1") (pin "6") (pinfunction "GPB5_6") (pintype "bidirectional"))
      (node (ref "ORN1") (pin "7") (pinfunction "2_7") (pintype "passive"))
    )
    (net (code "43") (name "GPB6") (class "Default")
      (node (ref "IC1") (pin "7") (pinfunction "GPB6_7") (pintype "bidirectional"))
      (node (ref "ORN1") (pin "6") (pinfunction "2_6") (pintype "passive"))
    )
    (net (code "44") (name "GPB7") (class "Default")
      (node (ref "IC1") (pin "8") (pinfunction "GPB7_8") (pintype "bidirectional"))
      (node (ref "ORN1") (pin "5") (pinfunction "2_5") (pintype "passive"))
    )
    (net (code "45") (name "IO5") (class "Default")
      (node (ref "OK4") (pin "15") (pinfunction "EMIT_15") (pintype "passive"))
      (node (ref "ORN6") (pin "8") (pinfunction "2_8") (pintype "passive"))
      (node (ref "U1") (pin "4") (pinfunction "4B_4") (pintype "input"))
    )
    (net (code "46") (name "IO6") (class "Default")
      (node (ref "OK4") (pin "13") (pinfunction "EMIT_13") (pintype "passive"))
      (node (ref "ORN6") (pin "2") (pinfunction "1_2") (pintype "passive"))
      (node (ref "U1") (pin "3") (pinfunction "3B_3") (pintype "input"))
    )
    (net (code "47") (name "IO7") (class "Default")
      (node (ref "OK4") (pin "11") (pinfunction "EMIT_11") (pintype "passive"))
      (node (ref "ORN6") (pin "3") (pinfunction "1_3") (pintype "passive"))
      (node (ref "U1") (pin "2") (pinfunction "2B_2") (pintype "input"))
    )
    (net (code "48") (name "IO8") (class "Default")
      (node (ref "OK4") (pin "9") (pinfunction "EMIT_9") (pintype "passive"))
      (node (ref "ORN6") (pin "4") (pinfunction "1_4") (pintype "passive"))
      (node (ref "U1") (pin "1") (pinfunction "1B_1") (pintype "input"))
    )
    (net (code "49") (name "LEDA") (class "Default")
      (node (ref "ER3") (pin "1") (pinfunction "1_1") (pintype "passive"))
      (node (ref "U$2") (pin "Y+") (pinfunction "Y+_Y+") (pintype "bidirectional"))
    )
    (net (code "50") (name "LEDB") (class "Default")
      (node (ref "ER4") (pin "1") (pinfunction "1_1") (pintype "passive"))
      (node (ref "U$2") (pin "G+") (pinfunction "G+_G+") (pintype "bidirectional"))
    )
    (net (code "51") (name "Net-(ENC-LEDA)") (class "Default")
      (node (ref "ENC") (pin "27") (pinfunction "LEDA_27") (pintype "output"))
      (node (ref "ER3") (pin "2") (pinfunction "2_2") (pintype "passive"))
    )
    (net (code "52") (name "Net-(ENC-LEDB)") (class "Default")
      (node (ref "ENC") (pin "26") (pinfunction "LEDB_26") (pintype "output"))
      (node (ref "ER4") (pin "2") (pinfunction "2_2") (pintype "passive"))
    )
    (net (code "53") (name "Net-(ENC-OSC1)") (class "Default")
      (node (ref "EC1") (pin "1") (pinfunction "1_1") (pintype "passive"))
      (node (ref "ENC") (pin "23") (pinfunction "OSC1_23") (pintype "input"))
      (node (ref "Q2") (pin "2") (pinfunction "2_2") (pintype "passive"))
    )
    (net (code "54") (name "Net-(ENC-OSC2)") (class "Default")
      (node (ref "EC2") (pin "1") (pinfunction "1_1") (pintype "passive"))
      (node (ref "ENC") (pin "24") (pinfunction "OSC2_24") (pintype "output"))
      (node (ref "Q2") (pin "1") (pinfunction "1_1") (pintype "passive"))
    )
    (net (code "55") (name "Net-(ENC-RBIAS)") (class "Default")
      (node (ref "ENC") (pin "14") (pinfunction "RBIAS_14") (pintype "passive"))
      (node (ref "ER10") (pin "1") (pinfunction "1_1") (pintype "passive"))
    )
    (net (code "56") (name "Net-(ENC-RESET)") (class "Default")
      (node (ref "ENC") (pin "10") (pinfunction "RESET_10") (pintype "input"))
      (node (ref "ER1") (pin "1") (pinfunction "1_1") (pintype "passive"))
    )
    (net (code "57") (name "Net-(ENC-TPIN+)") (class "Default")
      (node (ref "ENC") (pin "13") (pinfunction "TPIN+_13") (pintype "input"))
      (node (ref "ERN1") (pin "6") (pinfunction "2_6") (pintype "passive"))
      (node (ref "U$2") (pin "RD+") (pinfunction "RD+_RD+") (pintype "bidirectional"))
    )
    (net (code "58") (name "Net-(ENC-TPIN-)") (class "Default")
      (node (ref "ENC") (pin "12") (pinfunction "TPIN-_12") (pintype "input"))
      (node (ref "ERN1") (pin "5") (pinfunction "2_5") (pintype "passive"))
      (node (ref "U$2") (pin "RD-") (pinfunction "RD-_RD-") (pintype "bidirectional"))
    )
    (net (code "59") (name "Net-(ENC-TPOUT+)") (class "Default")
      (node (ref "ENC") (pin "17") (pinfunction "TPOUT+_17") (pintype "output"))
      (node (ref "ERN1") (pin "1") (pinfunction "1_1") (pintype "passive"))
      (node (ref "U$2") (pin "TD+") (pinfunction "TD+_TD+") (pintype "bidirectional"))
    )
    (net (code "60") (name "Net-(ENC-TPOUT-)") (class "Default")
      (node (ref "ENC") (pin "16") (pinfunction "TPOUT-_16") (pintype "output"))
      (node (ref "ERN1") (pin "2") (pinfunction "1_2") (pintype "passive"))
      (node (ref "U$2") (pin "TD-") (pinfunction "TD-_TD-") (pintype "bidirectional"))
    )
    (net (code "61") (name "Net-(ENC-VCAP)") (class "Default")
      (node (ref "EC3") (pin "+") (pinfunction "+_+") (pintype "passive"))
      (node (ref "ENC") (pin "1") (pinfunction "VCAP_1") (pintype "power_in"))
    )
    (net (code "62") (name "Net-(ERN1A-2)") (class "Default")
      (node (ref "EC4") (pin "1") (pinfunction "1_1") (pintype "passive"))
      (node (ref "EL1") (pin "2") (pinfunction "2_2") (pintype "passive"))
      (node (ref "ERN1") (pin "7") (pinfunction "2_7") (pintype "passive"))
      (node (ref "ERN1") (pin "8") (pinfunction "2_8") (pintype "passive"))
      (node (ref "U$2") (pin "P4") (pinfunction "P4_P4") (pintype "bidirectional"))
    )
    (net (code "63") (name "Net-(ERN1C-1)") (class "Default")
      (node (ref "EC5") (pin "1") (pinfunction "1_1") (pintype "passive"))
      (node (ref "ERN1") (pin "3") (pinfunction "1_3") (pintype "passive"))
      (node (ref "ERN1") (pin "4") (pinfunction "1_4") (pintype "passive"))
      (node (ref "U$2") (pin "P5") (pinfunction "P5_P5") (pintype "bidirectional"))
    )
    (net (code "64") (name "Net-(IC1-A0)") (class "Default")
      (node (ref "IC1") (pin "15") (pinfunction "A0_15") (pintype "input"))
      (node (ref "MR3") (pin "1") (pinfunction "1_1") (pintype "passive"))
    )
    (net (code "65") (name "Net-(IIR1A-2)") (class "Default")
      (node (ref "IIR1") (pin "8") (pinfunction "2_8") (pintype "passive"))
      (node (ref "OK1") (pin "1") (pinfunction "A_1") (pintype "passive"))
    )
    (net (code "66") (name "Net-(IIR1B-1)") (class "Default")
      (node (ref "IIR1") (pin "2") (pinfunction "1_2") (pintype "passive"))
      (node (ref "XI1") (pin "3") (pinfunction "SK_3") (pintype "passive"))
    )
    (net (code "67") (name "Net-(IIR1B-2)") (class "Default")
      (node (ref "IIR1") (pin "7") (pinfunction "2_7") (pintype "passive"))
      (node (ref "OK1") (pin "3") (pinfunction "A_3") (pintype "passive"))
    )
    (net (code "68") (name "Net-(IIR1C-1)") (class "Default")
      (node (ref "IIR1") (pin "3") (pinfunction "1_3") (pintype "passive"))
      (node (ref "XI1") (pin "4") (pinfunction "SK_4") (pintype "passive"))
    )
    (net (code "69") (name "Net-(IIR1C-2)") (class "Default")
      (node (ref "IIR1") (pin "6") (pinfunction "2_6") (pintype "passive"))
      (node (ref "OK1") (pin "5") (pinfunction "A_5") (pintype "passive"))
    )
    (net (code "70") (name "Net-(IIR1D-1)") (class "Default")
      (node (ref "IIR1") (pin "4") (pinfunction "1_4") (pintype "passive"))
      (node (ref "XI1") (pin "5") (pinfunction "SK_5") (pintype "passive"))
    )
    (net (code "71") (name "Net-(IIR1D-2)") (class "Default")
      (node (ref "IIR1") (pin "5") (pinfunction "2_5") (pintype "passive"))
      (node (ref "OK1") (pin "7") (pinfunction "A_7") (pintype "passive"))
    )
    (net (code "72") (name "Net-(IIR2A-2)") (class "Default")
      (node (ref "IIR2") (pin "8") (pinfunction "2_8") (pintype "passive"))
      (node (ref "OK2") (pin "1") (pinfunction "A_1") (pintype "passive"))
    )
    (net (code "73") (name "Net-(IIR2B-1)") (class "Default")
      (node (ref "IIR2") (pin "2") (pinfunction "1_2") (pintype "passive"))
      (node (ref "XI2") (pin "3") (pinfunction "SK_3") (pintype "passive"))
    )
    (net (code "74") (name "Net-(IIR2B-2)") (class "Default")
      (node (ref "IIR2") (pin "7") (pinfunction "2_7") (pintype "passive"))
      (node (ref "OK2") (pin "3") (pinfunction "A_3") (pintype "passive"))
    )
    (net (code "75") (name "Net-(IIR2C-1)") (class "Default")
      (node (ref "IIR2") (pin "3") (pinfunction "1_3") (pintype "passive"))
      (node (ref "XI2") (pin "4") (pinfunction "SK_4") (pintype "passive"))
    )
    (net (code "76") (name "Net-(IIR2C-2)") (class "Default")
      (node (ref "IIR2") (pin "6") (pinfunction "2_6") (pintype "passive"))
      (node (ref "OK2") (pin "5") (pinfunction "A_5") (pintype "passive"))
    )
    (net (code "77") (name "Net-(IIR2D-1)") (class "Default")
      (node (ref "IIR2") (pin "4") (pinfunction "1_4") (pintype "passive"))
      (node (ref "XI2") (pin "5") (pinfunction "SK_5") (pintype "passive"))
    )
    (net (code "78") (name "Net-(IIR2D-2)") (class "Default")
      (node (ref "IIR2") (pin "5") (pinfunction "2_5") (pintype "passive"))
      (node (ref "OK2") (pin "7") (pinfunction "A_7") (pintype "passive"))
    )
    (net (code "79") (name "Net-(INDL-PadA)") (class "Default")
      (node (ref "INDL") (pin "A") (pinfunction "A_A") (pintype "passive"))
      (node (ref "R6") (pin "2") (pinfunction "2_2") (pintype "passive"))
    )
    (net (code "80") (name "Net-(MC-PB6(XTAL1{slash}TOSC1))") (class "Default")
      (node (ref "MC") (pin "7") (pinfunction "PB6(XTAL1/TOSC1)_7") (pintype "bidirectional"))
      (node (ref "Q1") (pin "1") (pinfunction "1_1") (pintype "passive"))
    )
    (net (code "81") (name "Net-(MC-PB7(XTAL2{slash}TOSC2))") (class "Default")
      (node (ref "MC") (pin "8") (pinfunction "PB7(XTAL2/TOSC2)_8") (pintype "bidirectional"))
      (node (ref "Q1") (pin "3") (pinfunction "3_3") (pintype "passive"))
    )
    (net (code "82") (name "Net-(OD1-PadC)") (class "Default")
      (node (ref "OD1") (pin "C") (pinfunction "C_C") (pintype "passive"))
      (node (ref "OF1") (pin "2") (pinfunction "2_2") (pintype "bidirectional"))
    )
    (net (code "83") (name "Net-(OK1A-EMIT)") (class "Default")
      (node (ref "IL1") (pin "A") (pinfunction "A_A") (pintype "passive"))
      (node (ref "OK1") (pin "15") (pinfunction "EMIT_15") (pintype "passive"))
    )
    (net (code "84") (name "Net-(OK1B-EMIT)") (class "Default")
      (node (ref "IL2") (pin "A") (pinfunction "A_A") (pintype "passive"))
      (node (ref "OK1") (pin "13") (pinfunction "EMIT_13") (pintype "passive"))
    )
    (net (code "85") (name "Net-(OK1C-EMIT)") (class "Default")
      (node (ref "IL3") (pin "A") (pinfunction "A_A") (pintype "passive"))
      (node (ref "OK1") (pin "11") (pinfunction "EMIT_11") (pintype "passive"))
    )
    (net (code "86") (name "Net-(OK1D-EMIT)") (class "Default")
      (node (ref "IL4") (pin "A") (pinfunction "A_A") (pintype "passive"))
      (node (ref "OK1") (pin "9") (pinfunction "EMIT_9") (pintype "passive"))
    )
    (net (code "87") (name "Net-(OK2A-EMIT)") (class "Default")
      (node (ref "IL5") (pin "A") (pinfunction "A_A") (pintype "passive"))
      (node (ref "OK2") (pin "15") (pinfunction "EMIT_15") (pintype "passive"))
    )
    (net (code "88") (name "Net-(OK2B-EMIT)") (class "Default")
      (node (ref "IL6") (pin "A") (pinfunction "A_A") (pintype "passive"))
      (node (ref "OK2") (pin "13") (pinfunction "EMIT_13") (pintype "passive"))
    )
    (net (code "89") (name "Net-(OK2C-EMIT)") (class "Default")
      (node (ref "IL7") (pin "A") (pinfunction "A_A") (pintype "passive"))
      (node (ref "OK2") (pin "11") (pinfunction "EMIT_11") (pintype "passive"))
    )
    (net (code "90") (name "Net-(OK2D-EMIT)") (class "Default")
      (node (ref "IL8") (pin "A") (pinfunction "A_A") (pintype "passive"))
      (node (ref "OK2") (pin "9") (pinfunction "EMIT_9") (pintype "passive"))
    )
    (net (code "91") (name "Net-(OK3A-A)") (class "Default")
      (node (ref "OK3") (pin "1") (pinfunction "A_1") (pintype "passive"))
      (node (ref "ORN1") (pin "4") (pinfunction "1_4") (pintype "passive"))
    )
    (net (code "92") (name "Net-(OK3A-C)") (class "Default")
      (node (ref "OK3") (pin "2") (pinfunction "C_2") (pintype "passive"))
      (node (ref "OL1") (pin "A") (pinfunction "A_A") (pintype "passive"))
    )
    (net (code "93") (name "Net-(OK3A-COL)") (class "Default")
      (node (ref "OK3") (pin "16") (pinfunction "COL_16") (pintype "passive"))
      (node (ref "ORN3") (pin "1") (pinfunction "1_1") (pintype "passive"))
    )
    (net (code "94") (name "Net-(OK3B-A)") (class "Default")
      (node (ref "OK3") (pin "3") (pinfunction "A_3") (pintype "passive"))
      (node (ref "ORN1") (pin "3") (pinfunction "1_3") (pintype "passive"))
    )
    (net (code "95") (name "Net-(OK3B-C)") (class "Default")
      (node (ref "OK3") (pin "4") (pinfunction "C_4") (pintype "passive"))
      (node (ref "OL2") (pin "A") (pinfunction "A_A") (pintype "passive"))
    )
    (net (code "96") (name "Net-(OK3B-COL)") (class "Default")
      (node (ref "OK3") (pin "14") (pinfunction "COL_14") (pintype "passive"))
      (node (ref "ORN3") (pin "2") (pinfunction "1_2") (pintype "passive"))
    )
    (net (code "97") (name "Net-(OK3C-A)") (class "Default")
      (node (ref "OK3") (pin "5") (pinfunction "A_5") (pintype "passive"))
      (node (ref "ORN1") (pin "2") (pinfunction "1_2") (pintype "passive"))
    )
    (net (code "98") (name "Net-(OK3C-C)") (class "Default")
      (node (ref "OK3") (pin "6") (pinfunction "C_6") (pintype "passive"))
      (node (ref "OL3") (pin "A") (pinfunction "A_A") (pintype "passive"))
    )
    (net (code "99") (name "Net-(OK3C-COL)") (class "Default")
      (node (ref "OK3") (pin "12") (pinfunction "COL_12") (pintype "passive"))
      (node (ref "ORN3") (pin "3") (pinfunction "1_3") (pintype "passive"))
    )
    (net (code "100") (name "Net-(OK3D-A)") (class "Default")
      (node (ref "OK3") (pin "7") (pinfunction "A_7") (pintype "passive"))
      (node (ref "ORN1") (pin "1") (pinfunction "1_1") (pintype "passive"))
    )
    (net (code "101") (name "Net-(OK3D-C)") (class "Default")
      (node (ref "OK3") (pin "8") (pinfunction "C_8") (pintype "passive"))
      (node (ref "OL4") (pin "A") (pinfunction "A_A") (pintype "passive"))
    )
    (net (code "102") (name "Net-(OK3D-COL)") (class "Default")
      (node (ref "OK3") (pin "10") (pinfunction "COL_10") (pintype "passive"))
      (node (ref "ORN3") (pin "4") (pinfunction "1_4") (pintype "passive"))
    )
    (net (code "103") (name "Net-(OK4A-A)") (class "Default")
      (node (ref "OK4") (pin "1") (pinfunction "A_1") (pintype "passive"))
      (node (ref "ORN4") (pin "4") (pinfunction "1_4") (pintype "passive"))
    )
    (net (code "104") (name "Net-(OK4A-C)") (class "Default")
      (node (ref "OK4") (pin "2") (pinfunction "C_2") (pintype "passive"))
      (node (ref "OL5") (pin "A") (pinfunction "A_A") (pintype "passive"))
    )
    (net (code "105") (name "Net-(OK4A-COL)") (class "Default")
      (node (ref "OK4") (pin "16") (pinfunction "COL_16") (pintype "passive"))
      (node (ref "ORN5") (pin "1") (pinfunction "1_1") (pintype "passive"))
    )
    (net (code "106") (name "Net-(OK4B-A)") (class "Default")
      (node (ref "OK4") (pin "3") (pinfunction "A_3") (pintype "passive"))
      (node (ref "ORN4") (pin "3") (pinfunction "1_3") (pintype "passive"))
    )
    (net (code "107") (name "Net-(OK4B-C)") (class "Default")
      (node (ref "OK4") (pin "4") (pinfunction "C_4") (pintype "passive"))
      (node (ref "OL6") (pin "A") (pinfunction "A_A") (pintype "passive"))
    )
    (net (code "108") (name "Net-(OK4B-COL)") (class "Default")
      (node (ref "OK4") (pin "14") (pinfunction "COL_14") (pintype "passive"))
      (node (ref "ORN5") (pin "2") (pinfunction "1_2") (pintype "passive"))
    )
    (net (code "109") (name "Net-(OK4C-A)") (class "Default")
      (node (ref "OK4") (pin "5") (pinfunction "A_5") (pintype "passive"))
      (node (ref "ORN4") (pin "2") (pinfunction "1_2") (pintype "passive"))
    )
    (net (code "110") (name "Net-(OK4C-C)") (class "Default")
      (node (ref "OK4") (pin "6") (pinfunction "C_6") (pintype "passive"))
      (node (ref "OL7") (pin "A") (pinfunction "A_A") (pintype "passive"))
    )
    (net (code "111") (name "Net-(OK4C-COL)") (class "Default")
      (node (ref "OK4") (pin "12") (pinfunction "COL_12") (pintype "passive"))
      (node (ref "ORN5") (pin "3") (pinfunction "1_3") (pintype "passive"))
    )
    (net (code "112") (name "Net-(OK4D-A)") (class "Default")
      (node (ref "OK4") (pin "7") (pinfunction "A_7") (pintype "passive"))
      (node (ref "ORN4") (pin "1") (pinfunction "1_1") (pintype "passive"))
    )
    (net (code "113") (name "Net-(OK4D-C)") (class "Default")
      (node (ref "OK4") (pin "8") (pinfunction "C_8") (pintype "passive"))
      (node (ref "OL8") (pin "A") (pinfunction "A_A") (pintype "passive"))
    )
    (net (code "114") (name "Net-(OK4D-COL)") (class "Default")
      (node (ref "OK4") (pin "10") (pinfunction "COL_10") (pintype "passive"))
      (node (ref "ORN5") (pin "4") (pinfunction "1_4") (pintype "passive"))
    )
    (net (code "115") (name "Net-(PD1-PadC)") (class "Default")
      (node (ref "PD1") (pin "C") (pinfunction "C_C") (pintype "passive"))
      (node (ref "PF1") (pin "1") (pinfunction "1_1") (pintype "passive"))
    )
    (net (code "116") (name "Net-(PIC33-OUT)") (class "Default")
      (node (ref "PCO") (pin "P$2") (pinfunction "P$2_P$2") (pintype "passive"))
      (node (ref "PD2") (pin "C") (pinfunction "C_C") (pintype "passive"))
      (node (ref "PIC33") (pin "2") (pinfunction "OUT_2") (pintype "output"))
    )
    (net (code "117") (name "Net-(PL-PadA)") (class "Default")
      (node (ref "PL") (pin "A") (pinfunction "A_A") (pintype "passive"))
      (node (ref "PR1") (pin "1") (pinfunction "1_1") (pintype "passive"))
    )
    (net (code "118") (name "Net-(U1-1C)") (class "Default")
      (node (ref "D1") (pin "2") (pinfunction "2_2") (pintype "bidirectional"))
      (node (ref "OF3") (pin "2") (pinfunction "2_2") (pintype "bidirectional"))
      (node (ref "U1") (pin "18") (pinfunction "1C_18") (pintype "output"))
    )
    (net (code "119") (name "Net-(U1-2C)") (class "Default")
      (node (ref "D1") (pin "1") (pinfunction "1_1") (pintype "bidirectional"))
      (node (ref "OF2") (pin "2") (pinfunction "2_2") (pintype "bidirectional"))
      (node (ref "U1") (pin "17") (pinfunction "2C_17") (pintype "output"))
    )
    (net (code "120") (name "Net-(U1-3C)") (class "Default")
      (node (ref "D2") (pin "2") (pinfunction "2_2") (pintype "bidirectional"))
      (node (ref "OF4") (pin "2") (pinfunction "2_2") (pintype "bidirectional"))
      (node (ref "U1") (pin "16") (pinfunction "3C_16") (pintype "output"))
    )
    (net (code "121") (name "Net-(U1-4C)") (class "Default")
      (node (ref "D2") (pin "1") (pinfunction "1_1") (pintype "bidirectional"))
      (node (ref "OF5") (pin "2") (pinfunction "2_2") (pintype "bidirectional"))
      (node (ref "U1") (pin "15") (pinfunction "4C_15") (pintype "output"))
    )
    (net (code "122") (name "Net-(U1-5C)") (class "Default")
      (node (ref "D3") (pin "2") (pinfunction "2_2") (pintype "bidirectional"))
      (node (ref "OF6") (pin "2") (pinfunction "2_2") (pintype "bidirectional"))
      (node (ref "U1") (pin "14") (pinfunction "5C_14") (pintype "output"))
    )
    (net (code "123") (name "Net-(U1-6C)") (class "Default")
      (node (ref "D3") (pin "1") (pinfunction "1_1") (pintype "bidirectional"))
      (node (ref "OF7") (pin "2") (pinfunction "2_2") (pintype "bidirectional"))
      (node (ref "U1") (pin "13") (pinfunction "6C_13") (pintype "output"))
    )
    (net (code "124") (name "Net-(U1-7C)") (class "Default")
      (node (ref "D4") (pin "2") (pinfunction "2_2") (pintype "bidirectional"))
      (node (ref "OF8") (pin "2") (pinfunction "2_2") (pintype "bidirectional"))
      (node (ref "U1") (pin "12") (pinfunction "7C_12") (pintype "output"))
    )
    (net (code "125") (name "Net-(U1-8C)") (class "Default")
      (node (ref "D4") (pin "1") (pinfunction "1_1") (pintype "bidirectional"))
      (node (ref "OF9") (pin "2") (pinfunction "2_2") (pintype "bidirectional"))
      (node (ref "U1") (pin "11") (pinfunction "8C_11") (pintype "output"))
    )
    (net (code "126") (name "Net-(XI1B-SK)") (class "Default")
      (node (ref "IIR1") (pin "1") (pinfunction "1_1") (pintype "passive"))
      (node (ref "XI1") (pin "2") (pinfunction "SK_2") (pintype "passive"))
    )
    (net (code "127") (name "Net-(XI2B-SK)") (class "Default")
      (node (ref "IIR2") (pin "1") (pinfunction "1_1") (pintype "passive"))
      (node (ref "XI2") (pin "2") (pinfunction "SK_2") (pintype "passive"))
    )
    (net (code "128") (name "Net-(XOA-SK)") (class "Default")
      (node (ref "OD1") (pin "A") (pinfunction "A_A") (pintype "passive"))
      (node (ref "XO") (pin "1") (pinfunction "SK_1") (pintype "passive"))
    )
    (net (code "129") (name "Net-(XOB-SK)") (class "Default")
      (node (ref "OF3") (pin "1") (pinfunction "1_1") (pintype "bidirectional"))
      (node (ref "XO") (pin "10") (pinfunction "SK_10") (pintype "passive"))
    )
    (net (code "130") (name "Net-(XOD-SK)") (class "Default")
      (node (ref "OF9") (pin "1") (pinfunction "1_1") (pintype "bidirectional"))
      (node (ref "XO") (pin "3") (pinfunction "SK_3") (pintype "passive"))
    )
    (net (code "131") (name "Net-(XOE-SK)") (class "Default")
      (node (ref "OF8") (pin "1") (pinfunction "1_1") (pintype "bidirectional"))
      (node (ref "XO") (pin "4") (pinfunction "SK_4") (pintype "passive"))
    )
    (net (code "132") (name "Net-(XOF-SK)") (class "Default")
      (node (ref "OF7") (pin "1") (pinfunction "1_1") (pintype "bidirectional"))
      (node (ref "XO") (pin "5") (pinfunction "SK_5") (pintype "passive"))
    )
    (net (code "133") (name "Net-(XOG-SK)") (class "Default")
      (node (ref "OF6") (pin "1") (pinfunction "1_1") (pintype "bidirectional"))
      (node (ref "XO") (pin "6") (pinfunction "SK_6") (pintype "passive"))
    )
    (net (code "134") (name "Net-(XOH-SK)") (class "Default")
      (node (ref "OF5") (pin "1") (pinfunction "1_1") (pintype "bidirectional"))
      (node (ref "XO") (pin "7") (pinfunction "SK_7") (pintype "passive"))
    )
    (net (code "135") (name "Net-(XOI-SK)") (class "Default")
      (node (ref "OF4") (pin "1") (pinfunction "1_1") (pintype "bidirectional"))
      (node (ref "XO") (pin "8") (pinfunction "SK_8") (pintype "passive"))
    )
    (net (code "136") (name "Net-(XOJ-SK)") (class "Default")
      (node (ref "OF2") (pin "1") (pinfunction "1_1") (pintype "bidirectional"))
      (node (ref "XO") (pin "9") (pinfunction "SK_9") (pintype "passive"))
    )
    (net (code "137") (name "OI1") (class "Default")
      (node (ref "OK3") (pin "15") (pinfunction "EMIT_15") (pintype "passive"))
      (node (ref "ORN2") (pin "1") (pinfunction "1_1") (pintype "passive"))
      (node (ref "U1") (pin "8") (pinfunction "8B_8") (pintype "input"))
    )
    (net (code "138") (name "OI2") (class "Default")
      (node (ref "OK3") (pin "13") (pinfunction "EMIT_13") (pintype "passive"))
      (node (ref "ORN2") (pin "2") (pinfunction "1_2") (pintype "passive"))
      (node (ref "U1") (pin "7") (pinfunction "7B_7") (pintype "input"))
    )
    (net (code "139") (name "OI3") (class "Default")
      (node (ref "OK3") (pin "11") (pinfunction "EMIT_11") (pintype "passive"))
      (node (ref "ORN2") (pin "3") (pinfunction "1_3") (pintype "passive"))
      (node (ref "U1") (pin "6") (pinfunction "6B_6") (pintype "input"))
    )
    (net (code "140") (name "OI4") (class "Default")
      (node (ref "OK3") (pin "9") (pinfunction "EMIT_9") (pintype "passive"))
      (node (ref "ORN2") (pin "4") (pinfunction "1_4") (pintype "passive"))
      (node (ref "U1") (pin "5") (pinfunction "5B_5") (pintype "input"))
    )
    (net (code "141") (name "RAW_IV") (class "Default")
      (node (ref "GPIO") (pin "1") (pinfunction "S_1") (pintype "passive"))
      (node (ref "PC1") (pin "+") (pinfunction "+_+") (pintype "passive"))
      (node (ref "PF1") (pin "2") (pinfunction "2_2") (pintype "passive"))
      (node (ref "PIC33") (pin "1") (pinfunction "VIN_1") (pintype "input"))
    )
    (net (code "142") (name "RESET") (class "Default")
      (node (ref "BL") (pin "5") (pinfunction "S_5") (pintype "passive"))
      (node (ref "C2") (pin "1") (pinfunction "1_1") (pintype "passive"))
      (node (ref "MC") (pin "29") (pinfunction "PC6(/RESET)_29") (pintype "bidirectional"))
      (node (ref "R2") (pin "1") (pinfunction "1_1") (pintype "passive"))
      (node (ref "SR") (pin "1") (pinfunction "P_1") (pintype "passive"))
    )
    (net (code "143") (name "RXI") (class "Default")
      (node (ref "MC") (pin "30") (pinfunction "PD0(RXD)_30") (pintype "bidirectional"))
      (node (ref "PP") (pin "4") (pinfunction "S_4") (pintype "passive"))
    )
    (net (code "144") (name "TXO") (class "Default")
      (node (ref "MC") (pin "31") (pinfunction "PD1(TXD)_31") (pintype "bidirectional"))
      (node (ref "PP") (pin "3") (pinfunction "S_3") (pintype "passive"))
    )
    (net (code "145") (name "VDDO") (class "Default")
      (node (ref "D1") (pin "3") (pinfunction "3_3") (pintype "bidirectional"))
      (node (ref "D2") (pin "3") (pinfunction "3_3") (pintype "bidirectional"))
      (node (ref "D3") (pin "3") (pinfunction "3_3") (pintype "bidirectional"))
      (node (ref "D4") (pin "3") (pinfunction "3_3") (pintype "bidirectional"))
      (node (ref "EC6") (pin "+") (pinfunction "+_+") (pintype "passive"))
      (node (ref "OD2") (pin "C") (pinfunction "C_C") (pintype "passive"))
      (node (ref "OF1") (pin "1") (pinfunction "1_1") (pintype "bidirectional"))
      (node (ref "ORN3") (pin "5") (pinfunction "2_5") (pintype "passive"))
      (node (ref "ORN3") (pin "6") (pinfunction "2_6") (pintype "passive"))
      (node (ref "ORN3") (pin "7") (pinfunction "2_7") (pintype "passive"))
      (node (ref "ORN3") (pin "8") (pinfunction "2_8") (pintype "passive"))
      (node (ref "ORN5") (pin "5") (pinfunction "2_5") (pintype "passive"))
      (node (ref "ORN5") (pin "6") (pinfunction "2_6") (pintype "passive"))
      (node (ref "ORN5") (pin "7") (pinfunction "2_7") (pintype "passive"))
      (node (ref "ORN5") (pin "8") (pinfunction "2_8") (pintype "passive"))
      (node (ref "U1") (pin "10") (pinfunction "COM_10") (pintype "output"))
    )
    (net (code "146") (name "VIN") (class "Default")
      (node (ref "PD1") (pin "A") (pinfunction "A_A") (pintype "passive"))
      (node (ref "PJ1") (pin "VIN0") (pinfunction "PWR_VIN0") (pintype "bidirectional"))
      (node (ref "XV") (pin "2") (pinfunction "SK_2") (pintype "passive"))
    )
    (net (code "147") (name "WFGPIO0") (class "Default")
      (node (ref "GPIO") (pin "13") (pinfunction "S_13") (pintype "passive"))
      (node (ref "WIFI") (pin "GPIO0") (pinfunction "GPIO0_GPIO0") (pintype "bidirectional"))
    )
    (net (code "148") (name "WFGPIO2") (class "Default")
      (node (ref "GPIO") (pin "14") (pinfunction "S_14") (pintype "passive"))
      (node (ref "WIFI") (pin "GPIO2") (pinfunction "GPIO2_GPIO2") (pintype "bidirectional"))
    )
    (net (code "149") (name "unconnected-(ENC-CLKOUT-Pad3)") (class "Default")
      (node (ref "ENC") (pin "3") (pinfunction "CLKOUT_3") (pintype "output"))
    )
    (net (code "150") (name "unconnected-(ENC-WOL-Pad5)") (class "Default")
      (node (ref "ENC") (pin "5") (pinfunction "WOL_5") (pintype "output"))
    )
    (net (code "151") (name "unconnected-(IC1-INTA-Pad20)") (class "Default")
      (node (ref "IC1") (pin "20") (pinfunction "INTA_20") (pintype "output"))
    )
    (net (code "152") (name "unconnected-(PJ1-GND-PadP$4)") (class "Default")
      (node (ref "PJ1") (pin "P$4") (pinfunction "GND_P$4") (pintype "bidirectional"))
    )
    (net (code "153") (name "unconnected-(U$2-PadNC)") (class "Default")
      (node (ref "U$2") (pin "NC") (pinfunction "NC_NC") (pintype "bidirectional"))
    )
    (net (code "154") (name "unconnected-(WIFI-PadRST)") (class "Default")
      (node (ref "WIFI") (pin "RST") (pinfunction "RST_RST") (pintype "bidirectional"))
    )
  )
)
